# wtw-v01-00.net
KiCad netlist of a schematic drawn in EAGLE
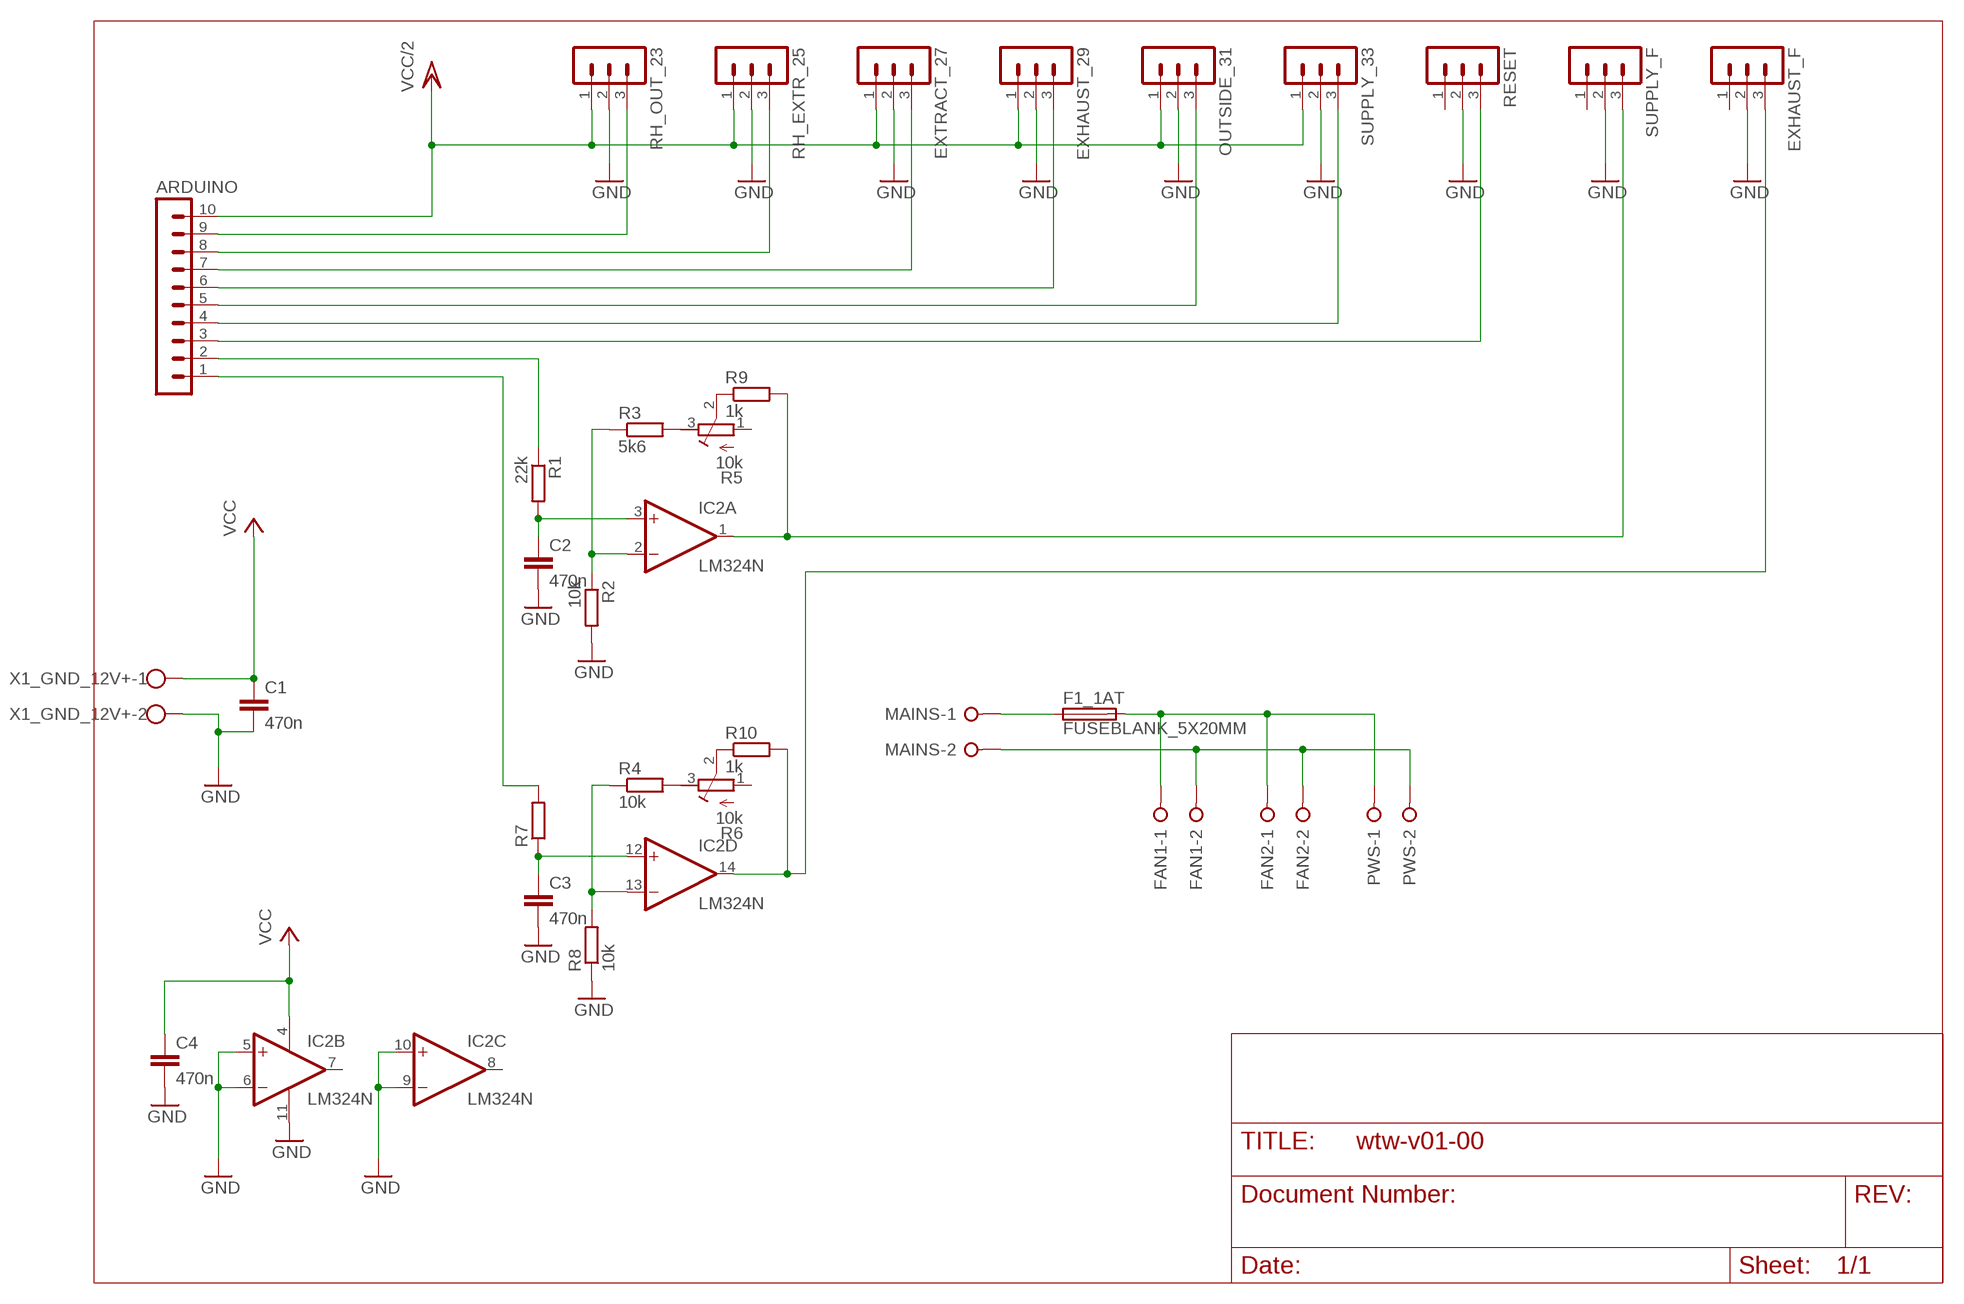
[diagram p0: schematic, sheet 1]

(export (version "E")
  (design (tool "Eeschema 10.0.6"))
  (components
    (comp (ref "ARDUINO")
      (value "MA10-1")
      (footprint "eagle-import:MA10-1")
      (libsource (lib "eagle-import") (part "MA10-1"))
    )
    (comp (ref "C1")
      (value "470n")
      (footprint "eagle-import:C050-030X075")
      (libsource (lib "eagle-import") (part "C-EU050-030X075"))
    )
    (comp (ref "C2")
      (value "470n")
      (footprint "eagle-import:C050-030X075")
      (libsource (lib "eagle-import") (part "C-EU050-030X075"))
    )
    (comp (ref "C3")
      (value "470n")
      (footprint "eagle-import:C050-030X075")
      (libsource (lib "eagle-import") (part "C-EU050-030X075"))
    )
    (comp (ref "C4")
      (value "470n")
      (footprint "eagle-import:C050-030X075")
      (libsource (lib "eagle-import") (part "C-EU050-030X075"))
    )
    (comp (ref "EXHAUST_29")
      (value "MA03-1")
      (footprint "eagle-import:MA03-1")
      (libsource (lib "eagle-import") (part "MA03-1"))
    )
    (comp (ref "EXHAUST_F")
      (value "MA03-1")
      (footprint "eagle-import:MA03-1")
      (libsource (lib "eagle-import") (part "MA03-1"))
    )
    (comp (ref "EXTRACT_27")
      (value "MA03-1")
      (footprint "eagle-import:MA03-1")
      (libsource (lib "eagle-import") (part "MA03-1"))
    )
    (comp (ref "F1_1AT")
      (value "FUSEBLANK_5X20MM")
      (footprint "eagle-import:FUSE_HOLDER_5X20MM")
      (libsource (lib "eagle-import") (part "FUSEBLANK_5X20MM"))
    )
    (comp (ref "FAN1")
      (value "W237-02P")
      (footprint "eagle-import:W237-132")
      (libsource (lib "eagle-import") (part "W237-02P"))
    )
    (comp (ref "FAN2")
      (value "W237-02P")
      (footprint "eagle-import:W237-132")
      (libsource (lib "eagle-import") (part "W237-02P"))
    )
    (comp (ref "IC2")
      (value "LM324N")
      (footprint "eagle-import:DIL14")
      (libsource (lib "eagle-import") (part "LM324N"))
    )
    (comp (ref "MAINS")
      (value "W237-02P")
      (footprint "eagle-import:W237-132")
      (libsource (lib "eagle-import") (part "W237-02P"))
    )
    (comp (ref "OUTSIDE_31")
      (value "MA03-1")
      (footprint "eagle-import:MA03-1")
      (libsource (lib "eagle-import") (part "MA03-1"))
    )
    (comp (ref "PWS")
      (value "W237-02P")
      (footprint "eagle-import:W237-132")
      (libsource (lib "eagle-import") (part "W237-02P"))
    )
    (comp (ref "R1")
      (value "22k")
      (footprint "eagle-import:V234_12")
      (libsource (lib "eagle-import") (part "R-EU_V234/12"))
    )
    (comp (ref "R2")
      (value "10k")
      (footprint "eagle-import:V234_12")
      (libsource (lib "eagle-import") (part "R-EU_V234/12"))
    )
    (comp (ref "R3")
      (value "5k6")
      (footprint "eagle-import:V234_12")
      (libsource (lib "eagle-import") (part "R-EU_V234/12"))
    )
    (comp (ref "R4")
      (value "10k")
      (footprint "eagle-import:V234_12")
      (libsource (lib "eagle-import") (part "R-EU_V234/12"))
    )
    (comp (ref "R5")
      (value "10k")
      (footprint "eagle-import:RTRIM64W")
      (libsource (lib "eagle-import") (part "R-TRIMM64W"))
    )
    (comp (ref "R6")
      (value "10k")
      (footprint "eagle-import:RTRIM64W")
      (libsource (lib "eagle-import") (part "R-TRIMM64W"))
    )
    (comp (ref "R7")
      (value "R-EU_V234/12")
      (footprint "eagle-import:V234_12")
      (libsource (lib "eagle-import") (part "R-EU_V234/12"))
    )
    (comp (ref "R8")
      (value "10k")
      (footprint "eagle-import:V234_12")
      (libsource (lib "eagle-import") (part "R-EU_V234/12"))
    )
    (comp (ref "R9")
      (value "1k")
      (footprint "eagle-import:V234_12")
      (libsource (lib "eagle-import") (part "R-EU_V234/12"))
    )
    (comp (ref "R10")
      (value "1k")
      (footprint "eagle-import:V234_12")
      (libsource (lib "eagle-import") (part "R-EU_V234/12"))
    )
    (comp (ref "RESET")
      (value "MA03-1")
      (footprint "eagle-import:MA03-1")
      (libsource (lib "eagle-import") (part "MA03-1"))
    )
    (comp (ref "RH_EXTR_25")
      (value "MA03-1")
      (footprint "eagle-import:MA03-1")
      (libsource (lib "eagle-import") (part "MA03-1"))
    )
    (comp (ref "RH_OUT_23")
      (value "MA03-1")
      (footprint "eagle-import:MA03-1")
      (libsource (lib "eagle-import") (part "MA03-1"))
    )
    (comp (ref "SUPPLY_33")
      (value "MA03-1")
      (footprint "eagle-import:MA03-1")
      (libsource (lib "eagle-import") (part "MA03-1"))
    )
    (comp (ref "SUPPLY_F")
      (value "MA03-1")
      (footprint "eagle-import:MA03-1")
      (libsource (lib "eagle-import") (part "MA03-1"))
    )
    (comp (ref "X1_GND_12V+")
      (value "W237-4")
      (footprint "eagle-import:W237-4")
      (libsource (lib "eagle-import") (part "W237-4"))
    )
  )
  (nets
    (net (code "1") (name "GND") (class "Default")
      (node (ref "C1") (pin "2") (pinfunction "2_2") (pintype "passive"))
      (node (ref "C2") (pin "2") (pinfunction "2_2") (pintype "passive"))
      (node (ref "C3") (pin "2") (pinfunction "2_2") (pintype "passive"))
      (node (ref "C4") (pin "2") (pinfunction "2_2") (pintype "passive"))
      (node (ref "EXHAUST_29") (pin "2") (pinfunction "2_2") (pintype "passive"))
      (node (ref "EXHAUST_F") (pin "2") (pinfunction "2_2") (pintype "passive"))
      (node (ref "EXTRACT_27") (pin "2") (pinfunction "2_2") (pintype "passive"))
      (node (ref "IC2") (pin "10") (pinfunction "+IN_10") (pintype "input"))
      (node (ref "IC2") (pin "11") (pinfunction "V-_11") (pintype "power_in"))
      (node (ref "IC2") (pin "5") (pinfunction "+IN_5") (pintype "input"))
      (node (ref "IC2") (pin "6") (pinfunction "-IN_6") (pintype "input"))
      (node (ref "IC2") (pin "9") (pinfunction "-IN_9") (pintype "input"))
      (node (ref "OUTSIDE_31") (pin "2") (pinfunction "2_2") (pintype "passive"))
      (node (ref "R2") (pin "2") (pinfunction "2_2") (pintype "passive"))
      (node (ref "R8") (pin "1") (pinfunction "1_1") (pintype "passive"))
      (node (ref "RESET") (pin "2") (pinfunction "2_2") (pintype "passive"))
      (node (ref "RH_EXTR_25") (pin "2") (pinfunction "2_2") (pintype "passive"))
      (node (ref "RH_OUT_23") (pin "2") (pinfunction "2_2") (pintype "passive"))
      (node (ref "SUPPLY_33") (pin "2") (pinfunction "2_2") (pintype "passive"))
      (node (ref "SUPPLY_F") (pin "2") (pinfunction "2_2") (pintype "passive"))
      (node (ref "X1_GND_12V+") (pin "2") (pinfunction "KL_2") (pintype "passive"))
    )
    (net (code "2") (name "Net-(ARDUINO-Pad1)") (class "Default")
      (node (ref "ARDUINO") (pin "1") (pinfunction "1_1") (pintype "passive"))
      (node (ref "R7") (pin "2") (pinfunction "2_2") (pintype "passive"))
    )
    (net (code "3") (name "Net-(ARDUINO-Pad2)") (class "Default")
      (node (ref "ARDUINO") (pin "2") (pinfunction "2_2") (pintype "passive"))
      (node (ref "R1") (pin "1") (pinfunction "1_1") (pintype "passive"))
    )
    (net (code "4") (name "Net-(ARDUINO-Pad3)") (class "Default")
      (node (ref "ARDUINO") (pin "3") (pinfunction "3_3") (pintype "passive"))
      (node (ref "RESET") (pin "3") (pinfunction "3_3") (pintype "passive"))
    )
    (net (code "5") (name "Net-(ARDUINO-Pad4)") (class "Default")
      (node (ref "ARDUINO") (pin "4") (pinfunction "4_4") (pintype "passive"))
      (node (ref "SUPPLY_33") (pin "3") (pinfunction "3_3") (pintype "passive"))
    )
    (net (code "6") (name "Net-(ARDUINO-Pad5)") (class "Default")
      (node (ref "ARDUINO") (pin "5") (pinfunction "5_5") (pintype "passive"))
      (node (ref "OUTSIDE_31") (pin "3") (pinfunction "3_3") (pintype "passive"))
    )
    (net (code "7") (name "Net-(ARDUINO-Pad6)") (class "Default")
      (node (ref "ARDUINO") (pin "6") (pinfunction "6_6") (pintype "passive"))
      (node (ref "EXHAUST_29") (pin "3") (pinfunction "3_3") (pintype "passive"))
    )
    (net (code "8") (name "Net-(ARDUINO-Pad7)") (class "Default")
      (node (ref "ARDUINO") (pin "7") (pinfunction "7_7") (pintype "passive"))
      (node (ref "EXTRACT_27") (pin "3") (pinfunction "3_3") (pintype "passive"))
    )
    (net (code "9") (name "Net-(ARDUINO-Pad8)") (class "Default")
      (node (ref "ARDUINO") (pin "8") (pinfunction "8_8") (pintype "passive"))
      (node (ref "RH_EXTR_25") (pin "3") (pinfunction "3_3") (pintype "passive"))
    )
    (net (code "10") (name "Net-(ARDUINO-Pad9)") (class "Default")
      (node (ref "ARDUINO") (pin "9") (pinfunction "9_9") (pintype "passive"))
      (node (ref "RH_OUT_23") (pin "3") (pinfunction "3_3") (pintype "passive"))
    )
    (net (code "11") (name "Net-(FAN1A-KL)") (class "Default")
      (node (ref "F1_1AT") (pin "2") (pinfunction "2_2") (pintype "passive"))
      (node (ref "FAN1") (pin "1") (pinfunction "KL_1") (pintype "passive"))
      (node (ref "FAN2") (pin "1") (pinfunction "KL_1") (pintype "passive"))
      (node (ref "PWS") (pin "1") (pinfunction "KL_1") (pintype "passive"))
    )
    (net (code "12") (name "Net-(FAN1B-KL)") (class "Default")
      (node (ref "FAN1") (pin "2") (pinfunction "KL_2") (pintype "passive"))
      (node (ref "FAN2") (pin "2") (pinfunction "KL_2") (pintype "passive"))
      (node (ref "MAINS") (pin "2") (pinfunction "KL_2") (pintype "passive"))
      (node (ref "PWS") (pin "2") (pinfunction "KL_2") (pintype "passive"))
    )
    (net (code "13") (name "Net-(IC2A-+IN)") (class "Default")
      (node (ref "C2") (pin "1") (pinfunction "1_1") (pintype "passive"))
      (node (ref "IC2") (pin "3") (pinfunction "+IN_3") (pintype "input"))
      (node (ref "R1") (pin "2") (pinfunction "2_2") (pintype "passive"))
    )
    (net (code "14") (name "Net-(IC2A--IN)") (class "Default")
      (node (ref "IC2") (pin "2") (pinfunction "-IN_2") (pintype "input"))
      (node (ref "R2") (pin "1") (pinfunction "1_1") (pintype "passive"))
      (node (ref "R3") (pin "1") (pinfunction "1_1") (pintype "passive"))
    )
    (net (code "15") (name "Net-(IC2A-OUT)") (class "Default")
      (node (ref "IC2") (pin "1") (pinfunction "OUT_1") (pintype "output"))
      (node (ref "R9") (pin "2") (pinfunction "2_2") (pintype "passive"))
      (node (ref "SUPPLY_F") (pin "3") (pinfunction "3_3") (pintype "passive"))
    )
    (net (code "16") (name "Net-(IC2D-+IN)") (class "Default")
      (node (ref "C3") (pin "1") (pinfunction "1_1") (pintype "passive"))
      (node (ref "IC2") (pin "12") (pinfunction "+IN_12") (pintype "input"))
      (node (ref "R7") (pin "1") (pinfunction "1_1") (pintype "passive"))
    )
    (net (code "17") (name "Net-(IC2D--IN)") (class "Default")
      (node (ref "IC2") (pin "13") (pinfunction "-IN_13") (pintype "input"))
      (node (ref "R4") (pin "1") (pinfunction "1_1") (pintype "passive"))
      (node (ref "R8") (pin "2") (pinfunction "2_2") (pintype "passive"))
    )
    (net (code "18") (name "Net-(IC2D-OUT)") (class "Default")
      (node (ref "EXHAUST_F") (pin "3") (pinfunction "3_3") (pintype "passive"))
      (node (ref "IC2") (pin "14") (pinfunction "OUT_14") (pintype "output"))
      (node (ref "R10") (pin "2") (pinfunction "2_2") (pintype "passive"))
    )
    (net (code "19") (name "Net-(MAINSA-KL)") (class "Default")
      (node (ref "F1_1AT") (pin "1") (pinfunction "1_1") (pintype "passive"))
      (node (ref "MAINS") (pin "1") (pinfunction "KL_1") (pintype "passive"))
    )
    (net (code "20") (name "Net-(R5-E)") (class "Default")
      (node (ref "R3") (pin "2") (pinfunction "2_2") (pintype "passive"))
      (node (ref "R5") (pin "3") (pinfunction "E_3") (pintype "passive"))
    )
    (net (code "21") (name "Net-(R5-S)") (class "Default")
      (node (ref "R5") (pin "2") (pinfunction "S_2") (pintype "passive"))
      (node (ref "R9") (pin "1") (pinfunction "1_1") (pintype "passive"))
    )
    (net (code "22") (name "Net-(R6-E)") (class "Default")
      (node (ref "R4") (pin "2") (pinfunction "2_2") (pintype "passive"))
      (node (ref "R6") (pin "3") (pinfunction "E_3") (pintype "passive"))
    )
    (net (code "23") (name "Net-(R6-S)") (class "Default")
      (node (ref "R10") (pin "1") (pinfunction "1_1") (pintype "passive"))
      (node (ref "R6") (pin "2") (pinfunction "S_2") (pintype "passive"))
    )
    (net (code "24") (name "VCC") (class "Default")
      (node (ref "C1") (pin "1") (pinfunction "1_1") (pintype "passive"))
      (node (ref "C4") (pin "1") (pinfunction "1_1") (pintype "passive"))
      (node (ref "IC2") (pin "4") (pinfunction "V+_4") (pintype "power_in"))
      (node (ref "X1_GND_12V+") (pin "1") (pinfunction "KL_1") (pintype "passive"))
    )
    (net (code "25") (name "VCC{slash}2") (class "Default")
      (node (ref "ARDUINO") (pin "10") (pinfunction "10_10") (pintype "passive"))
      (node (ref "EXHAUST_29") (pin "1") (pinfunction "1_1") (pintype "passive"))
      (node (ref "EXTRACT_27") (pin "1") (pinfunction "1_1") (pintype "passive"))
      (node (ref "OUTSIDE_31") (pin "1") (pinfunction "1_1") (pintype "passive"))
      (node (ref "RH_EXTR_25") (pin "1") (pinfunction "1_1") (pintype "passive"))
      (node (ref "RH_OUT_23") (pin "1") (pinfunction "1_1") (pintype "passive"))
      (node (ref "SUPPLY_33") (pin "1") (pinfunction "1_1") (pintype "passive"))
    )
    (net (code "26") (name "unconnected-(EXHAUST_F-Pad1)") (class "Default")
      (node (ref "EXHAUST_F") (pin "1") (pinfunction "1_1") (pintype "passive"))
    )
    (net (code "27") (name "unconnected-(IC2B-OUT-Pad7)") (class "Default")
      (node (ref "IC2") (pin "7") (pinfunction "OUT_7") (pintype "output"))
    )
    (net (code "28") (name "unconnected-(IC2C-OUT-Pad8)") (class "Default")
      (node (ref "IC2") (pin "8") (pinfunction "OUT_8") (pintype "output"))
    )
    (net (code "29") (name "unconnected-(R5-A-Pad1)") (class "Default")
      (node (ref "R5") (pin "1") (pinfunction "A_1") (pintype "passive"))
    )
    (net (code "30") (name "unconnected-(R6-A-Pad1)") (class "Default")
      (node (ref "R6") (pin "1") (pinfunction "A_1") (pintype "passive"))
    )
    (net (code "31") (name "unconnected-(RESET-Pad1)") (class "Default")
      (node (ref "RESET") (pin "1") (pinfunction "1_1") (pintype "passive"))
    )
    (net (code "32") (name "unconnected-(SUPPLY_F-Pad1)") (class "Default")
      (node (ref "SUPPLY_F") (pin "1") (pinfunction "1_1") (pintype "passive"))
    )
  )
)
